# Wattuino-Uno_v10.net
KiCad netlist of a schematic drawn in EAGLE
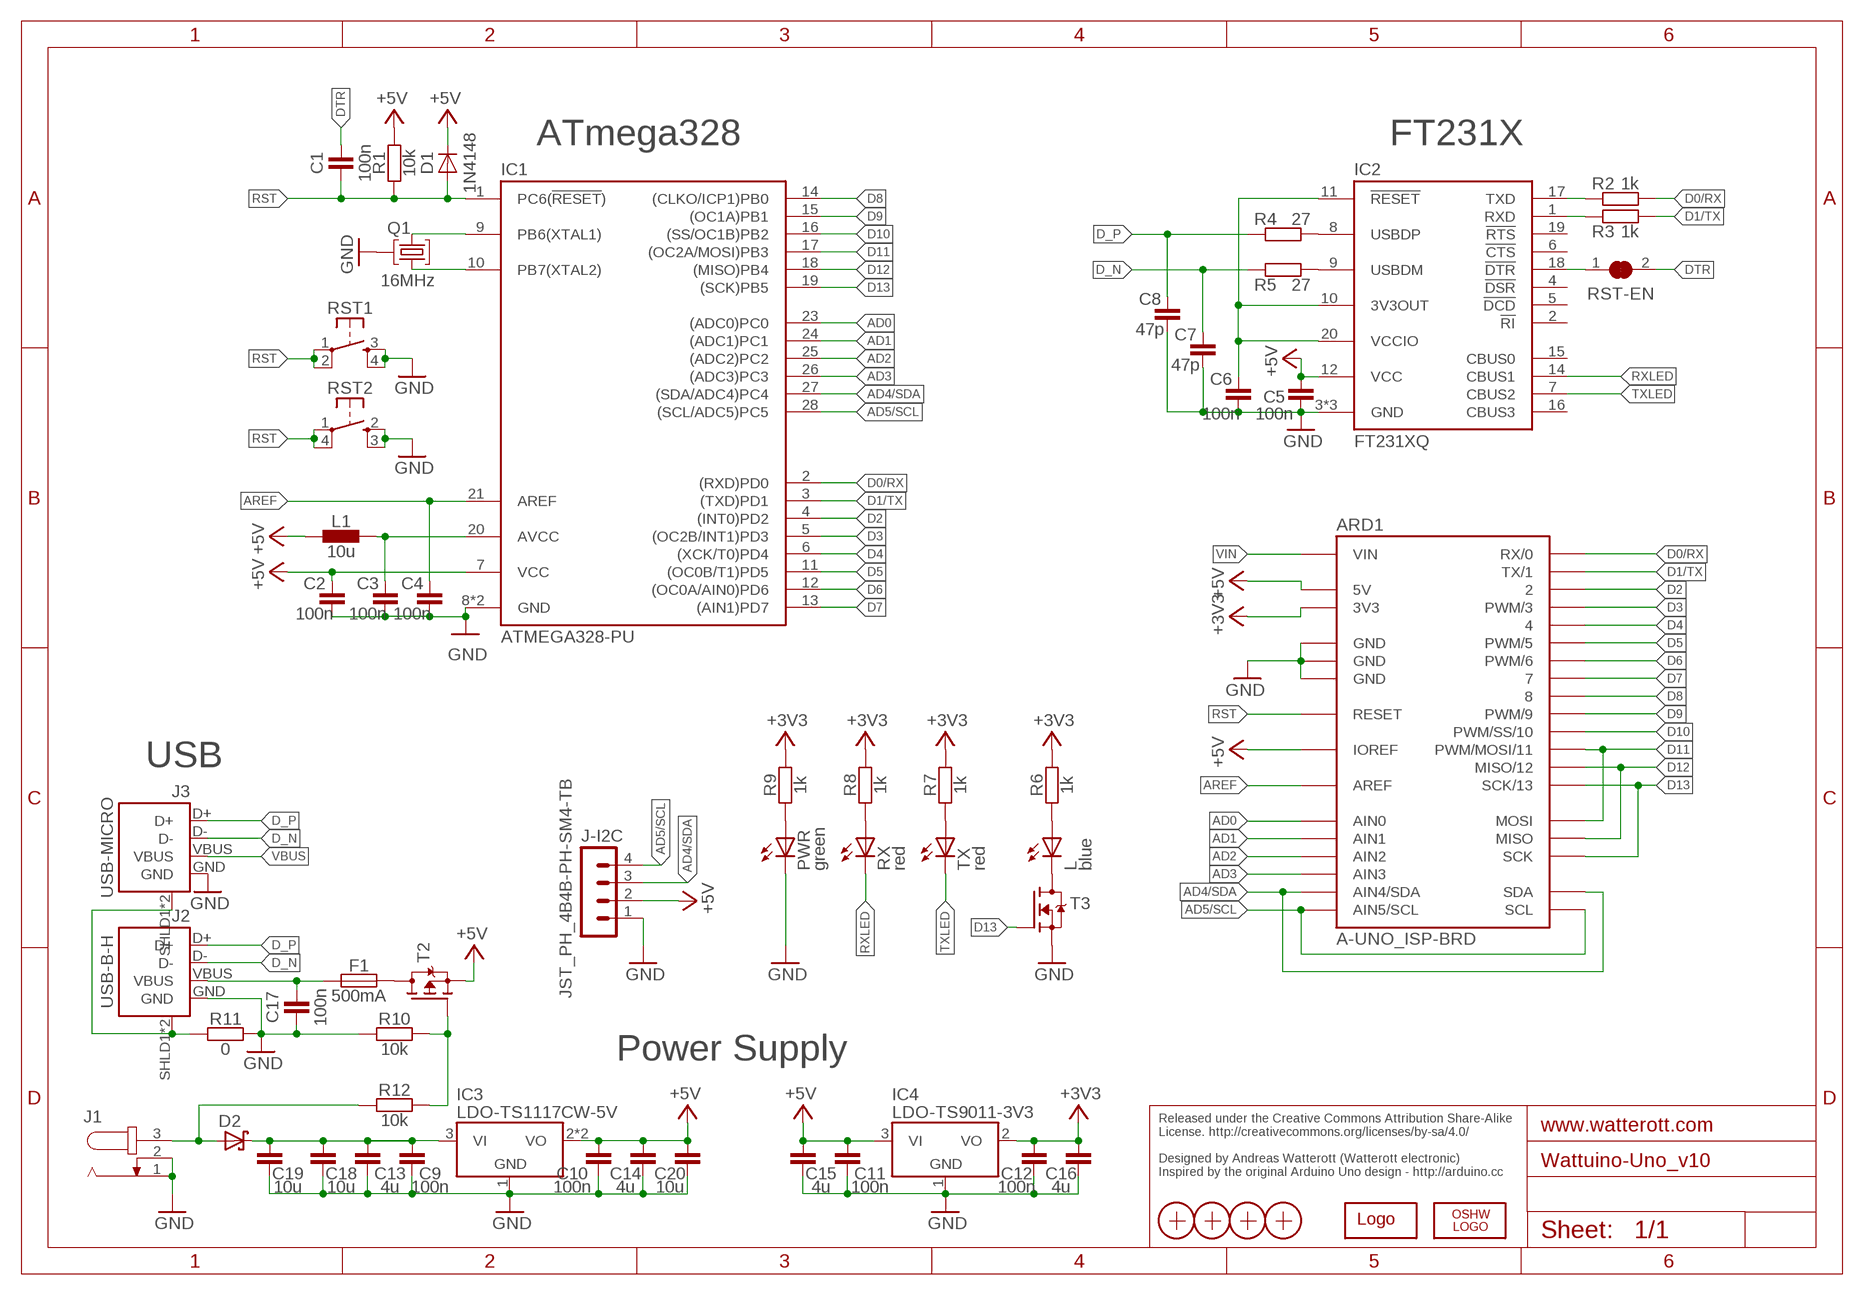
[diagram p0: schematic, sheet 1]

(export (version "E")
  (design (tool "Eeschema 10.0.6"))
  (components
    (comp (ref "ARD1")
      (value "A-UNO_ISP-BRD")
      (footprint "eagle-import:A-UNO-ISP")
      (libsource (lib "eagle-import") (part "A-UNO_ISP-BRD"))
    )
    (comp (ref "C1")
      (value "100n")
      (footprint "eagle-import:C0402")
      (libsource (lib "eagle-import") (part "CAPACITOR-0402"))
    )
    (comp (ref "C2")
      (value "100n")
      (footprint "eagle-import:C0402")
      (libsource (lib "eagle-import") (part "CAPACITOR-0402"))
    )
    (comp (ref "C3")
      (value "100n")
      (footprint "eagle-import:C0402")
      (libsource (lib "eagle-import") (part "CAPACITOR-0402"))
    )
    (comp (ref "C4")
      (value "100n")
      (footprint "eagle-import:C0402")
      (libsource (lib "eagle-import") (part "CAPACITOR-0402"))
    )
    (comp (ref "C5")
      (value "100n")
      (footprint "eagle-import:C0402")
      (libsource (lib "eagle-import") (part "CAPACITOR-0402"))
    )
    (comp (ref "C6")
      (value "100n")
      (footprint "eagle-import:C0402")
      (libsource (lib "eagle-import") (part "CAPACITOR-0402"))
    )
    (comp (ref "C7")
      (value "47p")
      (footprint "eagle-import:C0402")
      (libsource (lib "eagle-import") (part "CAPACITOR-0402"))
    )
    (comp (ref "C8")
      (value "47p")
      (footprint "eagle-import:C0402")
      (libsource (lib "eagle-import") (part "CAPACITOR-0402"))
    )
    (comp (ref "C9")
      (value "100n")
      (footprint "eagle-import:C0402")
      (libsource (lib "eagle-import") (part "CAPACITOR-0402"))
    )
    (comp (ref "C10")
      (value "100n")
      (footprint "eagle-import:C0402")
      (libsource (lib "eagle-import") (part "CAPACITOR-0402"))
    )
    (comp (ref "C11")
      (value "100n")
      (footprint "eagle-import:C0402")
      (libsource (lib "eagle-import") (part "CAPACITOR-0402"))
    )
    (comp (ref "C12")
      (value "100n")
      (footprint "eagle-import:C0402")
      (libsource (lib "eagle-import") (part "CAPACITOR-0402"))
    )
    (comp (ref "C13")
      (value "4u")
      (footprint "eagle-import:C0603")
      (libsource (lib "eagle-import") (part "CAPACITOR-0603"))
    )
    (comp (ref "C14")
      (value "4u")
      (footprint "eagle-import:C0603")
      (libsource (lib "eagle-import") (part "CAPACITOR-0603"))
    )
    (comp (ref "C15")
      (value "4u")
      (footprint "eagle-import:C0603")
      (libsource (lib "eagle-import") (part "CAPACITOR-0603"))
    )
    (comp (ref "C16")
      (value "4u")
      (footprint "eagle-import:C0603")
      (libsource (lib "eagle-import") (part "CAPACITOR-0603"))
    )
    (comp (ref "C17")
      (value "100n")
      (footprint "eagle-import:C0402")
      (libsource (lib "eagle-import") (part "CAPACITOR-0402"))
    )
    (comp (ref "C18")
      (value "10u")
      (footprint "eagle-import:C1206")
      (libsource (lib "eagle-import") (part "CAPACITOR-1206"))
    )
    (comp (ref "C19")
      (value "10u")
      (footprint "eagle-import:C1206")
      (libsource (lib "eagle-import") (part "CAPACITOR-1206"))
    )
    (comp (ref "C20")
      (value "10u")
      (footprint "eagle-import:C1206")
      (libsource (lib "eagle-import") (part "CAPACITOR-1206"))
    )
    (comp (ref "D1")
      (value "1N4148")
      (footprint "eagle-import:SOD110")
      (libsource (lib "eagle-import") (part "DIODE-SOD110"))
    )
    (comp (ref "D2")
      (value "D_SCHOTTKY-SS14")
      (footprint "eagle-import:SMA_DO214AC")
      (libsource (lib "eagle-import") (part "D_SCHOTTKY-SS14"))
    )
    (comp (ref "F1")
      (value "500mA")
      (footprint "eagle-import:C0805")
      (libsource (lib "eagle-import") (part "FUSE-0805"))
    )
    (comp (ref "IC1")
      (value "ATMEGA328-PU")
      (footprint "eagle-import:DIL28")
      (libsource (lib "eagle-import") (part "ATMEGA328-PU"))
    )
    (comp (ref "IC2")
      (value "FT231XQ")
      (footprint "eagle-import:QFN20-PAD")
      (libsource (lib "eagle-import") (part "FT231XQ"))
    )
    (comp (ref "IC3")
      (value "LDO-TS1117CW-5V")
      (footprint "eagle-import:SOT223")
      (libsource (lib "eagle-import") (part "LDO-TS1117CW-5V"))
    )
    (comp (ref "IC4")
      (value "LDO-TS9011-3V3")
      (footprint "eagle-import:SOT23")
      (libsource (lib "eagle-import") (part "LDO-TS9011-3V3"))
    )
    (comp (ref "J-I2C")
      (value "JST_PH_4B4B-PH-SM4-TB")
      (footprint "eagle-import:JST_B4B-PH-SM4-TB")
      (libsource (lib "eagle-import") (part "JST_PH_4B4B-PH-SM4-TB"))
    )
    (comp (ref "J1")
      (value "DC-JACK")
      (footprint "eagle-import:DC-JACK")
      (libsource (lib "eagle-import") (part "DC-JACK"))
    )
    (comp (ref "J2")
      (value "USB-B-H")
      (footprint "eagle-import:USB-B-H")
      (libsource (lib "eagle-import") (part "USB-B-H"))
    )
    (comp (ref "J3")
      (value "USB-MICRO")
      (footprint "eagle-import:USB-MICRO-10103594")
      (libsource (lib "eagle-import") (part "USB-MICRO"))
    )
    (comp (ref "L")
      (value "blue")
      (footprint "eagle-import:C0603")
      (libsource (lib "eagle-import") (part "LED-0603"))
    )
    (comp (ref "L1")
      (value "10u")
      (footprint "eagle-import:C0603")
      (libsource (lib "eagle-import") (part "INDUCTOR-0603"))
    )
    (comp (ref "LOGO1")
      (value "LOGO-S_PLACE_M")
      (footprint "eagle-import:SPARK_TPLACE_M")
      (libsource (lib "eagle-import") (part "LOGO-S_PLACE_M"))
    )
    (comp (ref "LOGO2")
      (value "OSHW_LOGOX0100")
      (footprint "eagle-import:OSHW_6X100")
      (libsource (lib "eagle-import") (part "OSHW_LOGOX0100"))
    )
    (comp (ref "PWR")
      (value "green")
      (footprint "eagle-import:C0603")
      (libsource (lib "eagle-import") (part "LED-0603"))
    )
    (comp (ref "Q1")
      (value "16MHz")
      (footprint "eagle-import:CRYSTAL_32X13")
      (libsource (lib "eagle-import") (part "CRYSTAL-RES-32"))
    )
    (comp (ref "R1")
      (value "10k")
      (footprint "eagle-import:C0402")
      (libsource (lib "eagle-import") (part "RESISTOR-0402"))
    )
    (comp (ref "R2")
      (value "1k")
      (footprint "eagle-import:C0402")
      (libsource (lib "eagle-import") (part "RESISTOR-0402"))
    )
    (comp (ref "R3")
      (value "1k")
      (footprint "eagle-import:C0402")
      (libsource (lib "eagle-import") (part "RESISTOR-0402"))
    )
    (comp (ref "R4")
      (value "27")
      (footprint "eagle-import:C0402")
      (libsource (lib "eagle-import") (part "RESISTOR-0402"))
    )
    (comp (ref "R5")
      (value "27")
      (footprint "eagle-import:C0402")
      (libsource (lib "eagle-import") (part "RESISTOR-0402"))
    )
    (comp (ref "R6")
      (value "1k")
      (footprint "eagle-import:C0402")
      (libsource (lib "eagle-import") (part "RESISTOR-0402"))
    )
    (comp (ref "R7")
      (value "1k")
      (footprint "eagle-import:C0402")
      (libsource (lib "eagle-import") (part "RESISTOR-0402"))
    )
    (comp (ref "R8")
      (value "1k")
      (footprint "eagle-import:C0402")
      (libsource (lib "eagle-import") (part "RESISTOR-0402"))
    )
    (comp (ref "R9")
      (value "1k")
      (footprint "eagle-import:C0402")
      (libsource (lib "eagle-import") (part "RESISTOR-0402"))
    )
    (comp (ref "R10")
      (value "10k")
      (footprint "eagle-import:C0402")
      (libsource (lib "eagle-import") (part "RESISTOR-0402"))
    )
    (comp (ref "R11")
      (value "0")
      (footprint "eagle-import:C0402")
      (libsource (lib "eagle-import") (part "RESISTOR-0402"))
    )
    (comp (ref "R12")
      (value "10k")
      (footprint "eagle-import:C0402")
      (libsource (lib "eagle-import") (part "RESISTOR-0402"))
    )
    (comp (ref "RST-EN")
      (value "JUMPER2-0603")
      (footprint "eagle-import:JUMPER2-0603")
      (libsource (lib "eagle-import") (part "JUMPER2-0603"))
    )
    (comp (ref "RST1")
      (value "SW-TACTILE-PTS840P")
      (footprint "eagle-import:SW_PTS840P")
      (libsource (lib "eagle-import") (part "SW-TACTILE-PTS840P"))
    )
    (comp (ref "RST2")
      (value "SW-TACTILE-TL3315")
      (footprint "eagle-import:SW_TL3315N")
      (libsource (lib "eagle-import") (part "SW-TACTILE-TL3315"))
    )
    (comp (ref "RX")
      (value "red")
      (footprint "eagle-import:C0603")
      (libsource (lib "eagle-import") (part "LED-0603"))
    )
    (comp (ref "T2")
      (value "MOSFET-P-SOT23")
      (footprint "eagle-import:SOT23")
      (libsource (lib "eagle-import") (part "MOSFET-P-SOT23"))
    )
    (comp (ref "T3")
      (value "MOSFET-N-SOT23")
      (footprint "eagle-import:SOT23")
      (libsource (lib "eagle-import") (part "MOSFET-N-SOT23"))
    )
    (comp (ref "TX")
      (value "red")
      (footprint "eagle-import:C0603")
      (libsource (lib "eagle-import") (part "LED-0603"))
    )
    (comp (ref "X1")
      (value "PASSER-07")
      (footprint "eagle-import:PASSER_07MM")
      (libsource (lib "eagle-import") (part "PASSER-07"))
    )
    (comp (ref "X2")
      (value "PASSER-07")
      (footprint "eagle-import:PASSER_07MM")
      (libsource (lib "eagle-import") (part "PASSER-07"))
    )
    (comp (ref "X3")
      (value "PASSER-07")
      (footprint "eagle-import:PASSER_07MM")
      (libsource (lib "eagle-import") (part "PASSER-07"))
    )
    (comp (ref "X4")
      (value "PASSER-07")
      (footprint "eagle-import:PASSER_07MM")
      (libsource (lib "eagle-import") (part "PASSER-07"))
    )
  )
  (nets
    (net (code "1") (name "+3V3") (class "Default")
      (node (ref "ARD1") (pin "3V3") (pinfunction "3V3_3V3") (pintype "power_in"))
      (node (ref "C12") (pin "2") (pinfunction "2_2") (pintype "passive"))
      (node (ref "C16") (pin "2") (pinfunction "2_2") (pintype "passive"))
      (node (ref "IC4") (pin "2") (pinfunction "VO_2") (pintype "passive"))
      (node (ref "R6") (pin "2") (pinfunction "2_2") (pintype "passive"))
      (node (ref "R7") (pin "2") (pinfunction "2_2") (pintype "passive"))
      (node (ref "R8") (pin "2") (pinfunction "2_2") (pintype "passive"))
      (node (ref "R9") (pin "2") (pinfunction "2_2") (pintype "passive"))
    )
    (net (code "2") (name "+5V") (class "Default")
      (node (ref "ARD1") (pin "5V") (pinfunction "5V_5V") (pintype "power_in"))
      (node (ref "ARD1") (pin "IOREF") (pinfunction "IOREF_IOREF") (pintype "power_in"))
      (node (ref "ARD1") (pin "VCC") (pinfunction "5V_VCC") (pintype "power_in"))
      (node (ref "C10") (pin "2") (pinfunction "2_2") (pintype "passive"))
      (node (ref "C11") (pin "2") (pinfunction "2_2") (pintype "passive"))
      (node (ref "C14") (pin "2") (pinfunction "2_2") (pintype "passive"))
      (node (ref "C15") (pin "2") (pinfunction "2_2") (pintype "passive"))
      (node (ref "C2") (pin "2") (pinfunction "2_2") (pintype "passive"))
      (node (ref "C20") (pin "2") (pinfunction "2_2") (pintype "passive"))
      (node (ref "C5") (pin "2") (pinfunction "2_2") (pintype "passive"))
      (node (ref "D1") (pin "C") (pinfunction "C_C") (pintype "passive"))
      (node (ref "IC1") (pin "7") (pinfunction "VCC_7") (pintype "power_in"))
      (node (ref "IC2") (pin "12") (pinfunction "VCC_12") (pintype "power_in"))
      (node (ref "IC3") (pin "2") (pinfunction "VO_2") (pintype "passive"))
      (node (ref "IC3") (pin "4") (pinfunction "VO_4") (pintype "passive"))
      (node (ref "IC4") (pin "3") (pinfunction "VI_3") (pintype "input"))
      (node (ref "J-I2C") (pin "2") (pinfunction "2_2") (pintype "passive"))
      (node (ref "L1") (pin "1") (pinfunction "1_1") (pintype "passive"))
      (node (ref "R1") (pin "2") (pinfunction "2_2") (pintype "passive"))
      (node (ref "T2") (pin "2") (pinfunction "S_2") (pintype "passive"))
    )
    (net (code "3") (name "AD0") (class "Default")
      (node (ref "ARD1") (pin "A0") (pinfunction "AIN0_A0") (pintype "bidirectional"))
      (node (ref "IC1") (pin "23") (pinfunction "(ADC0)PC0_23") (pintype "bidirectional"))
    )
    (net (code "4") (name "AD1") (class "Default")
      (node (ref "ARD1") (pin "A1") (pinfunction "AIN1_A1") (pintype "bidirectional"))
      (node (ref "IC1") (pin "24") (pinfunction "(ADC1)PC1_24") (pintype "bidirectional"))
    )
    (net (code "5") (name "AD2") (class "Default")
      (node (ref "ARD1") (pin "A2") (pinfunction "AIN2_A2") (pintype "bidirectional"))
      (node (ref "IC1") (pin "25") (pinfunction "(ADC2)PC2_25") (pintype "bidirectional"))
    )
    (net (code "6") (name "AD3") (class "Default")
      (node (ref "ARD1") (pin "A3") (pinfunction "AIN3_A3") (pintype "bidirectional"))
      (node (ref "IC1") (pin "26") (pinfunction "(ADC3)PC3_26") (pintype "bidirectional"))
    )
    (net (code "7") (name "AD4{slash}SDA") (class "Default")
      (node (ref "ARD1") (pin "A4") (pinfunction "AIN4/SDA_A4") (pintype "bidirectional"))
      (node (ref "ARD1") (pin "SDA") (pinfunction "SDA_SDA") (pintype "bidirectional"))
      (node (ref "IC1") (pin "27") (pinfunction "(SDA/ADC4)PC4_27") (pintype "bidirectional"))
      (node (ref "J-I2C") (pin "3") (pinfunction "3_3") (pintype "passive"))
    )
    (net (code "8") (name "AD5{slash}SCL") (class "Default")
      (node (ref "ARD1") (pin "A5") (pinfunction "AIN5/SCL_A5") (pintype "bidirectional"))
      (node (ref "ARD1") (pin "SCL") (pinfunction "SCL_SCL") (pintype "bidirectional"))
      (node (ref "IC1") (pin "28") (pinfunction "(SCL/ADC5)PC5_28") (pintype "bidirectional"))
      (node (ref "J-I2C") (pin "4") (pinfunction "4_4") (pintype "passive"))
    )
    (net (code "9") (name "AREF") (class "Default")
      (node (ref "ARD1") (pin "AREF") (pinfunction "AREF_AREF") (pintype "power_in"))
      (node (ref "C4") (pin "2") (pinfunction "2_2") (pintype "passive"))
      (node (ref "IC1") (pin "21") (pinfunction "AREF_21") (pintype "passive"))
    )
    (net (code "10") (name "D0{slash}RX") (class "Default")
      (node (ref "ARD1") (pin "0") (pinfunction "RX/0_0") (pintype "bidirectional"))
      (node (ref "IC1") (pin "2") (pinfunction "(RXD)PD0_2") (pintype "bidirectional"))
      (node (ref "R2") (pin "2") (pinfunction "2_2") (pintype "passive"))
    )
    (net (code "11") (name "D1{slash}TX") (class "Default")
      (node (ref "ARD1") (pin "1") (pinfunction "TX/1_1") (pintype "bidirectional"))
      (node (ref "IC1") (pin "3") (pinfunction "(TXD)PD1_3") (pintype "bidirectional"))
      (node (ref "R3") (pin "2") (pinfunction "2_2") (pintype "passive"))
    )
    (net (code "12") (name "D2") (class "Default")
      (node (ref "ARD1") (pin "2") (pinfunction "2_2") (pintype "bidirectional"))
      (node (ref "IC1") (pin "4") (pinfunction "(INT0)PD2_4") (pintype "bidirectional"))
    )
    (net (code "13") (name "D3") (class "Default")
      (node (ref "ARD1") (pin "3") (pinfunction "PWM/3_3") (pintype "bidirectional"))
      (node (ref "IC1") (pin "5") (pinfunction "(OC2B/INT1)PD3_5") (pintype "bidirectional"))
    )
    (net (code "14") (name "D4") (class "Default")
      (node (ref "ARD1") (pin "4") (pinfunction "4_4") (pintype "bidirectional"))
      (node (ref "IC1") (pin "6") (pinfunction "(XCK/T0)PD4_6") (pintype "bidirectional"))
    )
    (net (code "15") (name "D5") (class "Default")
      (node (ref "ARD1") (pin "5") (pinfunction "PWM/5_5") (pintype "bidirectional"))
      (node (ref "IC1") (pin "11") (pinfunction "(OC0B/T1)PD5_11") (pintype "bidirectional"))
    )
    (net (code "16") (name "D6") (class "Default")
      (node (ref "ARD1") (pin "6") (pinfunction "PWM/6_6") (pintype "bidirectional"))
      (node (ref "IC1") (pin "12") (pinfunction "(OC0A/AIN0)PD6_12") (pintype "bidirectional"))
    )
    (net (code "17") (name "D7") (class "Default")
      (node (ref "ARD1") (pin "7") (pinfunction "7_7") (pintype "bidirectional"))
      (node (ref "IC1") (pin "13") (pinfunction "(AIN1)PD7_13") (pintype "bidirectional"))
    )
    (net (code "18") (name "D8") (class "Default")
      (node (ref "ARD1") (pin "8") (pinfunction "8_8") (pintype "bidirectional"))
      (node (ref "IC1") (pin "14") (pinfunction "(CLKO/ICP1)PB0_14") (pintype "bidirectional"))
    )
    (net (code "19") (name "D9") (class "Default")
      (node (ref "ARD1") (pin "9") (pinfunction "PWM/9_9") (pintype "bidirectional"))
      (node (ref "IC1") (pin "15") (pinfunction "(OC1A)PB1_15") (pintype "bidirectional"))
    )
    (net (code "20") (name "D10") (class "Default")
      (node (ref "ARD1") (pin "10") (pinfunction "PWM/SS/10_10") (pintype "bidirectional"))
      (node (ref "IC1") (pin "16") (pinfunction "(SS/OC1B)PB2_16") (pintype "bidirectional"))
    )
    (net (code "21") (name "D11") (class "Default")
      (node (ref "ARD1") (pin "11") (pinfunction "PWM/MOSI/11_11") (pintype "bidirectional"))
      (node (ref "ARD1") (pin "MOSI") (pinfunction "MOSI_MOSI") (pintype "bidirectional"))
      (node (ref "IC1") (pin "17") (pinfunction "(OC2A/MOSI)PB3_17") (pintype "bidirectional"))
    )
    (net (code "22") (name "D12") (class "Default")
      (node (ref "ARD1") (pin "12") (pinfunction "MISO/12_12") (pintype "bidirectional"))
      (node (ref "ARD1") (pin "MISO") (pinfunction "MISO_MISO") (pintype "bidirectional"))
      (node (ref "IC1") (pin "18") (pinfunction "(MISO)PB4_18") (pintype "bidirectional"))
    )
    (net (code "23") (name "D13") (class "Default")
      (node (ref "ARD1") (pin "13") (pinfunction "SCK/13_13") (pintype "bidirectional"))
      (node (ref "ARD1") (pin "SCK") (pinfunction "SCK_SCK") (pintype "bidirectional"))
      (node (ref "IC1") (pin "19") (pinfunction "(SCK)PB5_19") (pintype "bidirectional"))
      (node (ref "T3") (pin "1") (pinfunction "G_1") (pintype "passive"))
    )
    (net (code "24") (name "DTR") (class "Default")
      (node (ref "C1") (pin "2") (pinfunction "2_2") (pintype "passive"))
      (node (ref "RST-EN") (pin "2") (pinfunction "2_2") (pintype "passive"))
    )
    (net (code "25") (name "D_N") (class "Default")
      (node (ref "C7") (pin "2") (pinfunction "2_2") (pintype "passive"))
      (node (ref "J2") (pin "D-") (pinfunction "D-_D-") (pintype "bidirectional"))
      (node (ref "J3") (pin "D-") (pinfunction "D-_D-") (pintype "bidirectional"))
      (node (ref "R5") (pin "1") (pinfunction "1_1") (pintype "passive"))
    )
    (net (code "26") (name "D_P") (class "Default")
      (node (ref "C8") (pin "2") (pinfunction "2_2") (pintype "passive"))
      (node (ref "J2") (pin "D+") (pinfunction "D+_D+") (pintype "bidirectional"))
      (node (ref "J3") (pin "D+") (pinfunction "D+_D+") (pintype "bidirectional"))
      (node (ref "R4") (pin "1") (pinfunction "1_1") (pintype "passive"))
    )
    (net (code "27") (name "GND") (class "Default")
      (node (ref "ARD1") (pin "GND@1") (pinfunction "GND_GND@1") (pintype "power_in"))
      (node (ref "ARD1") (pin "GND@2") (pinfunction "GND_GND@2") (pintype "power_in"))
      (node (ref "ARD1") (pin "GND@3") (pinfunction "GND_GND@3") (pintype "power_in"))
      (node (ref "ARD1") (pin "GND@4") (pinfunction "GND_GND@4") (pintype "power_in"))
      (node (ref "C10") (pin "1") (pinfunction "1_1") (pintype "passive"))
      (node (ref "C11") (pin "1") (pinfunction "1_1") (pintype "passive"))
      (node (ref "C12") (pin "1") (pinfunction "1_1") (pintype "passive"))
      (node (ref "C13") (pin "1") (pinfunction "1_1") (pintype "passive"))
      (node (ref "C14") (pin "1") (pinfunction "1_1") (pintype "passive"))
      (node (ref "C15") (pin "1") (pinfunction "1_1") (pintype "passive"))
      (node (ref "C16") (pin "1") (pinfunction "1_1") (pintype "passive"))
      (node (ref "C17") (pin "1") (pinfunction "1_1") (pintype "passive"))
      (node (ref "C18") (pin "1") (pinfunction "1_1") (pintype "passive"))
      (node (ref "C19") (pin "1") (pinfunction "1_1") (pintype "passive"))
      (node (ref "C2") (pin "1") (pinfunction "1_1") (pintype "passive"))
      (node (ref "C20") (pin "1") (pinfunction "1_1") (pintype "passive"))
      (node (ref "C3") (pin "1") (pinfunction "1_1") (pintype "passive"))
      (node (ref "C4") (pin "1") (pinfunction "1_1") (pintype "passive"))
      (node (ref "C5") (pin "1") (pinfunction "1_1") (pintype "passive"))
      (node (ref "C6") (pin "1") (pinfunction "1_1") (pintype "passive"))
      (node (ref "C7") (pin "1") (pinfunction "1_1") (pintype "passive"))
      (node (ref "C8") (pin "1") (pinfunction "1_1") (pintype "passive"))
      (node (ref "C9") (pin "1") (pinfunction "1_1") (pintype "passive"))
      (node (ref "IC1") (pin "22") (pinfunction "GND_22") (pintype "power_in"))
      (node (ref "IC1") (pin "8") (pinfunction "GND_8") (pintype "power_in"))
      (node (ref "IC2") (pin "13") (pinfunction "GND_13") (pintype "power_in"))
      (node (ref "IC2") (pin "3") (pinfunction "GND_3") (pintype "power_in"))
      (node (ref "IC2") (pin "TP") (pinfunction "GND_TP") (pintype "power_in"))
      (node (ref "IC3") (pin "1") (pinfunction "GND_1") (pintype "passive"))
      (node (ref "IC4") (pin "1") (pinfunction "GND_1") (pintype "passive"))
      (node (ref "J-I2C") (pin "1") (pinfunction "1_1") (pintype "passive"))
      (node (ref "J1") (pin "1") (pinfunction "1_1") (pintype "passive"))
      (node (ref "J1") (pin "2") (pinfunction "2_2") (pintype "passive"))
      (node (ref "J2") (pin "GND") (pinfunction "GND_GND") (pintype "power_in"))
      (node (ref "J3") (pin "GND") (pinfunction "GND_GND") (pintype "power_in"))
      (node (ref "PWR") (pin "C") (pinfunction "C_C") (pintype "passive"))
      (node (ref "Q1") (pin "GND") (pinfunction "GND_GND") (pintype "passive"))
      (node (ref "R10") (pin "1") (pinfunction "1_1") (pintype "passive"))
      (node (ref "R11") (pin "2") (pinfunction "2_2") (pintype "passive"))
      (node (ref "RST1") (pin "3") (pinfunction "S1_3") (pintype "passive"))
      (node (ref "RST1") (pin "4") (pinfunction "S2_4") (pintype "passive"))
      (node (ref "RST2") (pin "2") (pinfunction "S1_2") (pintype "passive"))
      (node (ref "RST2") (pin "3") (pinfunction "S2_3") (pintype "passive"))
      (node (ref "T3") (pin "2") (pinfunction "S_2") (pintype "passive"))
    )
    (net (code "28") (name "Net-(D2-PadA)") (class "Default")
      (node (ref "D2") (pin "A") (pinfunction "A_A") (pintype "passive"))
      (node (ref "J1") (pin "3") (pinfunction "3_3") (pintype "passive"))
      (node (ref "R12") (pin "1") (pinfunction "1_1") (pintype "passive"))
    )
    (net (code "29") (name "Net-(IC1-AVCC)") (class "Default")
      (node (ref "C3") (pin "2") (pinfunction "2_2") (pintype "passive"))
      (node (ref "IC1") (pin "20") (pinfunction "AVCC_20") (pintype "power_in"))
      (node (ref "L1") (pin "2") (pinfunction "2_2") (pintype "passive"))
    )
    (net (code "30") (name "Net-(IC1-PB6(XTAL1))") (class "Default")
      (node (ref "IC1") (pin "9") (pinfunction "PB6(XTAL1)_9") (pintype "bidirectional"))
      (node (ref "Q1") (pin "2") (pinfunction "2_2") (pintype "passive"))
    )
    (net (code "31") (name "Net-(IC1-PB7(XTAL2))") (class "Default")
      (node (ref "IC1") (pin "10") (pinfunction "PB7(XTAL2)_10") (pintype "bidirectional"))
      (node (ref "Q1") (pin "1") (pinfunction "1_1") (pintype "passive"))
    )
    (net (code "32") (name "Net-(IC2-3V3OUT)") (class "Default")
      (node (ref "C6") (pin "2") (pinfunction "2_2") (pintype "passive"))
      (node (ref "IC2") (pin "10") (pinfunction "3V3OUT_10") (pintype "power_in"))
      (node (ref "IC2") (pin "11") (pinfunction "~{RESET}_11") (pintype "bidirectional"))
      (node (ref "IC2") (pin "20") (pinfunction "VCCIO_20") (pintype "power_in"))
    )
    (net (code "33") (name "Net-(IC2-RXD)") (class "Default")
      (node (ref "IC2") (pin "1") (pinfunction "RXD_1") (pintype "bidirectional"))
      (node (ref "R3") (pin "1") (pinfunction "1_1") (pintype "passive"))
    )
    (net (code "34") (name "Net-(IC2-TXD)") (class "Default")
      (node (ref "IC2") (pin "17") (pinfunction "TXD_17") (pintype "bidirectional"))
      (node (ref "R2") (pin "1") (pinfunction "1_1") (pintype "passive"))
    )
    (net (code "35") (name "Net-(IC2-USBDM)") (class "Default")
      (node (ref "IC2") (pin "9") (pinfunction "USBDM_9") (pintype "bidirectional"))
      (node (ref "R5") (pin "2") (pinfunction "2_2") (pintype "passive"))
    )
    (net (code "36") (name "Net-(IC2-USBDP)") (class "Default")
      (node (ref "IC2") (pin "8") (pinfunction "USBDP_8") (pintype "bidirectional"))
      (node (ref "R4") (pin "2") (pinfunction "2_2") (pintype "passive"))
    )
    (net (code "37") (name "Net-(IC2-~{DTR})") (class "Default")
      (node (ref "IC2") (pin "18") (pinfunction "~{DTR}_18") (pintype "bidirectional"))
      (node (ref "RST-EN") (pin "1") (pinfunction "1_1") (pintype "passive"))
    )
    (net (code "38") (name "Net-(J2-SHIELD-PadSHLD1)") (class "Default")
      (node (ref "J2") (pin "SHLD1") (pinfunction "SHIELD_SHLD1") (pintype "passive"))
      (node (ref "J2") (pin "SHLD2") (pinfunction "SHIELD_SHLD2") (pintype "passive"))
      (node (ref "J3") (pin "SHLD1") (pinfunction "SHIELD_SHLD1") (pintype "passive"))
      (node (ref "J3") (pin "SHLD2") (pinfunction "SHIELD_SHLD2") (pintype "passive"))
      (node (ref "R11") (pin "1") (pinfunction "1_1") (pintype "passive"))
    )
    (net (code "39") (name "Net-(L-PadA)") (class "Default")
      (node (ref "L") (pin "A") (pinfunction "A_A") (pintype "passive"))
      (node (ref "R6") (pin "1") (pinfunction "1_1") (pintype "passive"))
    )
    (net (code "40") (name "Net-(PWR-PadA)") (class "Default")
      (node (ref "PWR") (pin "A") (pinfunction "A_A") (pintype "passive"))
      (node (ref "R9") (pin "1") (pinfunction "1_1") (pintype "passive"))
    )
    (net (code "41") (name "Net-(R7-Pad1)") (class "Default")
      (node (ref "R7") (pin "1") (pinfunction "1_1") (pintype "passive"))
      (node (ref "TX") (pin "A") (pinfunction "A_A") (pintype "passive"))
    )
    (net (code "42") (name "Net-(R8-Pad1)") (class "Default")
      (node (ref "R8") (pin "1") (pinfunction "1_1") (pintype "passive"))
      (node (ref "RX") (pin "A") (pinfunction "A_A") (pintype "passive"))
    )
    (net (code "43") (name "Net-(T2-D)") (class "Default")
      (node (ref "F1") (pin "2") (pinfunction "2_2") (pintype "passive"))
      (node (ref "T2") (pin "3") (pinfunction "D_3") (pintype "passive"))
    )
    (net (code "44") (name "Net-(T2-G)") (class "Default")
      (node (ref "R10") (pin "2") (pinfunction "2_2") (pintype "passive"))
      (node (ref "R12") (pin "2") (pinfunction "2_2") (pintype "passive"))
      (node (ref "T2") (pin "1") (pinfunction "G_1") (pintype "passive"))
    )
    (net (code "45") (name "Net-(T3-D)") (class "Default")
      (node (ref "L") (pin "C") (pinfunction "C_C") (pintype "passive"))
      (node (ref "T3") (pin "3") (pinfunction "D_3") (pintype "passive"))
    )
    (net (code "46") (name "RST") (class "Default")
      (node (ref "ARD1") (pin "RST") (pinfunction "RESET_RST") (pintype "bidirectional"))
      (node (ref "ARD1") (pin "RST2") (pinfunction "RESET_RST2") (pintype "bidirectional"))
      (node (ref "C1") (pin "1") (pinfunction "1_1") (pintype "passive"))
      (node (ref "D1") (pin "A") (pinfunction "A_A") (pintype "passive"))
      (node (ref "IC1") (pin "1") (pinfunction "PC6(~{RESET})_1") (pintype "bidirectional"))
      (node (ref "R1") (pin "1") (pinfunction "1_1") (pintype "passive"))
      (node (ref "RST1") (pin "1") (pinfunction "P1_1") (pintype "passive"))
      (node (ref "RST1") (pin "2") (pinfunction "P2_2") (pintype "passive"))
      (node (ref "RST2") (pin "1") (pinfunction "P1_1") (pintype "passive"))
      (node (ref "RST2") (pin "4") (pinfunction "P2_4") (pintype "passive"))
    )
    (net (code "47") (name "RXLED") (class "Default")
      (node (ref "IC2") (pin "14") (pinfunction "CBUS1_14") (pintype "bidirectional"))
      (node (ref "RX") (pin "C") (pinfunction "C_C") (pintype "passive"))
    )
    (net (code "48") (name "TXLED") (class "Default")
      (node (ref "IC2") (pin "7") (pinfunction "CBUS2_7") (pintype "bidirectional"))
      (node (ref "TX") (pin "C") (pinfunction "C_C") (pintype "passive"))
    )
    (net (code "49") (name "VBUS") (class "Default")
      (node (ref "C17") (pin "2") (pinfunction "2_2") (pintype "passive"))
      (node (ref "F1") (pin "1") (pinfunction "1_1") (pintype "passive"))
      (node (ref "J2") (pin "VBUS") (pinfunction "VBUS_VBUS") (pintype "power_in"))
      (node (ref "J3") (pin "VBUS") (pinfunction "VBUS_VBUS") (pintype "power_in"))
    )
    (net (code "50") (name "VIN") (class "Default")
      (node (ref "ARD1") (pin "VIN") (pinfunction "VIN_VIN") (pintype "power_in"))
      (node (ref "C13") (pin "2") (pinfunction "2_2") (pintype "passive"))
      (node (ref "C18") (pin "2") (pinfunction "2_2") (pintype "passive"))
      (node (ref "C19") (pin "2") (pinfunction "2_2") (pintype "passive"))
      (node (ref "C9") (pin "2") (pinfunction "2_2") (pintype "passive"))
      (node (ref "D2") (pin "C") (pinfunction "C_C") (pintype "passive"))
      (node (ref "IC3") (pin "3") (pinfunction "VI_3") (pintype "input"))
    )
    (net (code "51") (name "unconnected-(IC2-CBUS0-Pad15)") (class "Default")
      (node (ref "IC2") (pin "15") (pinfunction "CBUS0_15") (pintype "bidirectional"))
    )
    (net (code "52") (name "unconnected-(IC2-CBUS3-Pad16)") (class "Default")
      (node (ref "IC2") (pin "16") (pinfunction "CBUS3_16") (pintype "bidirectional"))
    )
    (net (code "53") (name "unconnected-(IC2-~{CTS}-Pad6)") (class "Default")
      (node (ref "IC2") (pin "6") (pinfunction "~{CTS}_6") (pintype "bidirectional"))
    )
    (net (code "54") (name "unconnected-(IC2-~{DCD}-Pad5)") (class "Default")
      (node (ref "IC2") (pin "5") (pinfunction "~{DCD}_5") (pintype "bidirectional"))
    )
    (net (code "55") (name "unconnected-(IC2-~{DSR}-Pad4)") (class "Default")
      (node (ref "IC2") (pin "4") (pinfunction "~{DSR}_4") (pintype "bidirectional"))
    )
    (net (code "56") (name "unconnected-(IC2-~{RI}-Pad2)") (class "Default")
      (node (ref "IC2") (pin "2") (pinfunction "~{RI}_2") (pintype "bidirectional"))
    )
    (net (code "57") (name "unconnected-(IC2-~{RTS}-Pad19)") (class "Default")
      (node (ref "IC2") (pin "19") (pinfunction "~{RTS}_19") (pintype "bidirectional"))
    )
  )
)
